# Sled_Terminals_v1.net
KiCad netlist of a schematic drawn in EAGLE
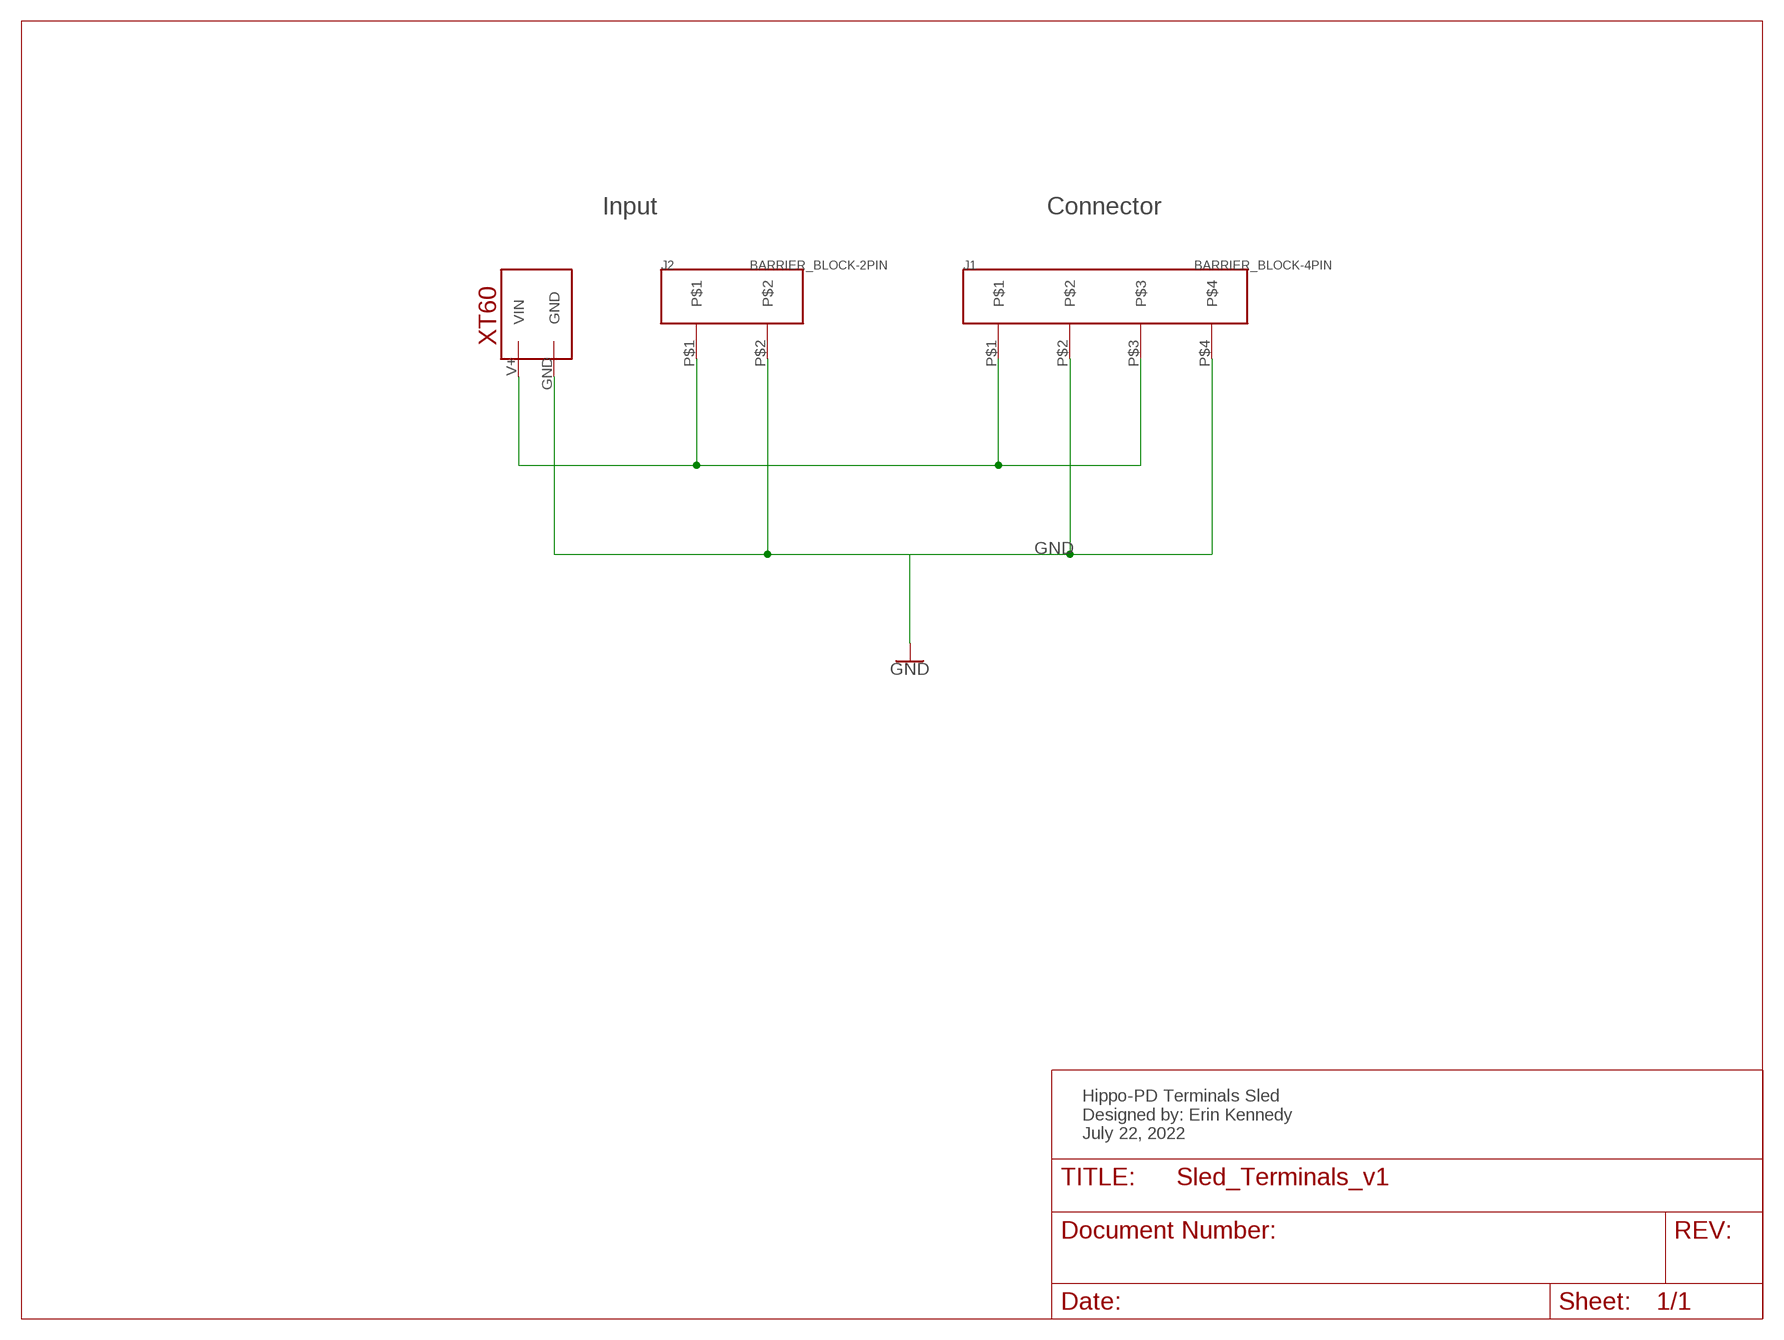
[diagram p0: schematic, sheet 1]

(export (version "E")
  (design (tool "Eeschema 10.0.6"))
  (components
    (comp (ref "J1")
      (value "BARRIER_BLOCK-4PIN")
      (footprint "eagle-import:BARRIERBLOCK-4PIN")
      (libsource (lib "eagle-import") (part "BARRIER_BLOCK-4PIN"))
    )
    (comp (ref "J2")
      (value "BARRIER_BLOCK-2PIN")
      (footprint "eagle-import:BARRIERBLOCK-2PIN")
      (libsource (lib "eagle-import") (part "BARRIER_BLOCK-2PIN"))
    )
    (comp (ref "U$1")
      (value "XT60")
      (footprint "eagle-import:XT60")
      (libsource (lib "eagle-import") (part "XT60"))
    )
  )
  (nets
    (net (code "1") (name "GND") (class "Default")
      (node (ref "J1") (pin "P$2") (pinfunction "P$2_P$2") (pintype "bidirectional"))
      (node (ref "J1") (pin "P$4") (pinfunction "P$4_P$4") (pintype "bidirectional"))
      (node (ref "J2") (pin "P$2") (pinfunction "P$2_P$2") (pintype "bidirectional"))
      (node (ref "U$1") (pin "GND") (pinfunction "GND_GND") (pintype "bidirectional"))
    )
    (net (code "2") (name "Net-(U$1-VIN)") (class "Default")
      (node (ref "J1") (pin "P$1") (pinfunction "P$1_P$1") (pintype "bidirectional"))
      (node (ref "J1") (pin "P$3") (pinfunction "P$3_P$3") (pintype "bidirectional"))
      (node (ref "J2") (pin "P$1") (pinfunction "P$1_P$1") (pintype "bidirectional"))
      (node (ref "U$1") (pin "V+") (pinfunction "VIN_V+") (pintype "bidirectional"))
    )
  )
)
